# STM32.net
KiCad netlist of a schematic drawn in Altium Designer
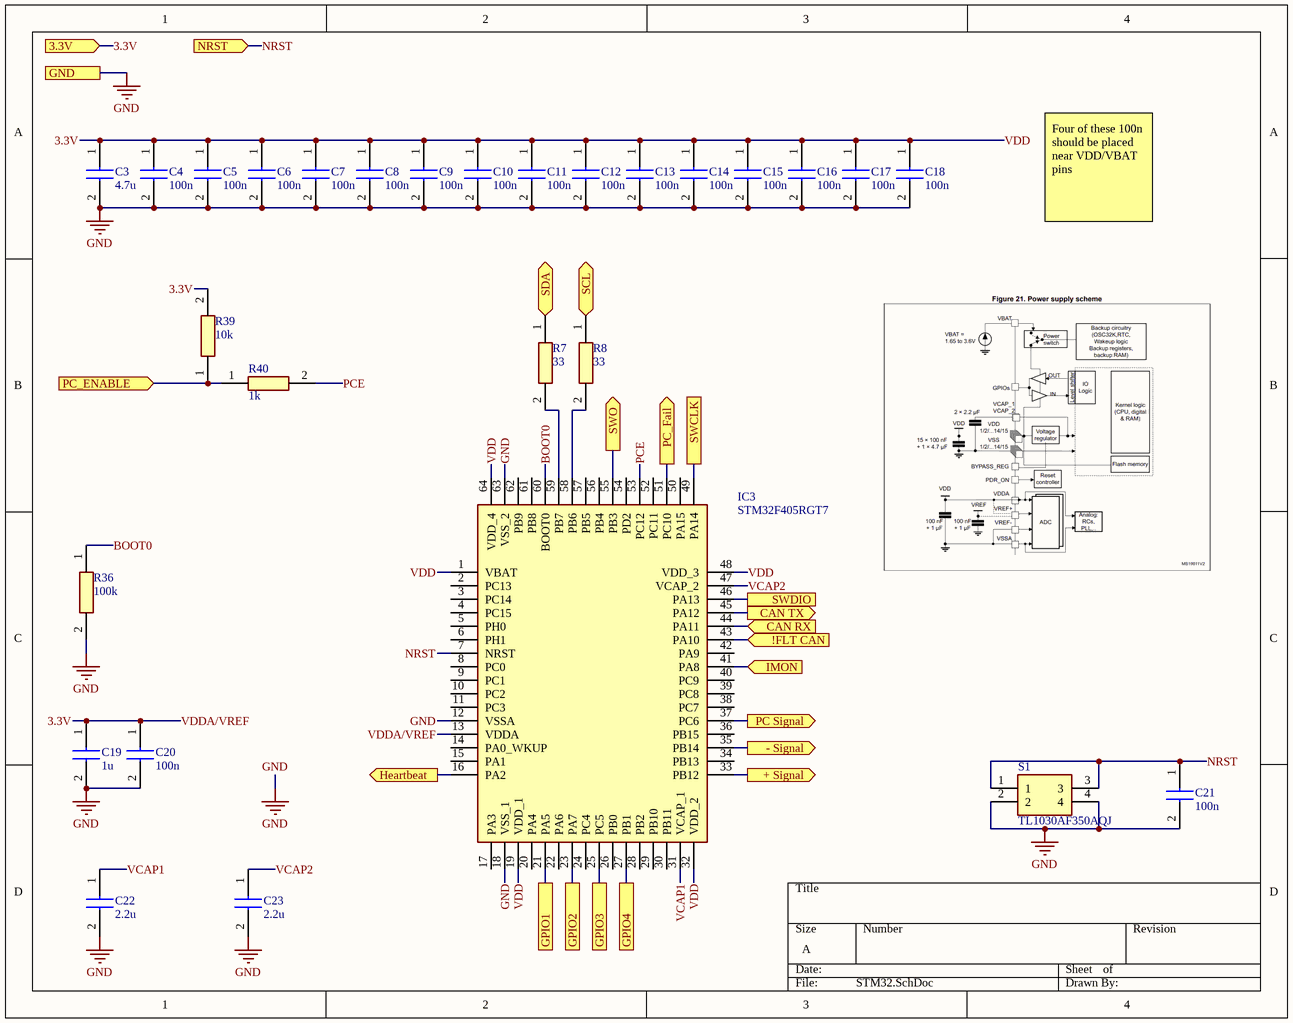
[diagram p0: STM32.SchDoc]

(export (version "E")
  (design (tool "Eeschema 10.0.6"))
  (components
    (comp (ref "C3")
      (value "4.7u")
      (footprint "SamacSys:CAPC3216X180N")
      (description "Capacitor")
      (fields
        (field (name "MANUFACTURER_PART_NUMBER") "GMK316AB7475KLHT")
        (field (name "MOUSER PART NUMBER") "963-GMK316AB7475KLHT")
      )
      (libsource (lib "SamacSys") (part "GMK316AB7475KLHT"))
    )
    (comp (ref "C4")
      (value "100n")
      (footprint "SamacSys:CAPC3216X94N")
      (description "Capacitor")
      (fields
        (field (name "MANUFACTURER_PART_NUMBER") "12065C104J4Z2A")
        (field (name "MOUSER PART NUMBER") "581-12065C104J4Z2A")
      )
      (libsource (lib "SamacSys") (part "12065C104J4Z2A"))
    )
    (comp (ref "C5")
      (value "100n")
      (footprint "SamacSys:CAPC3216X94N")
      (description "Capacitor")
      (fields
        (field (name "MANUFACTURER_PART_NUMBER") "12065C104J4Z2A")
        (field (name "MOUSER PART NUMBER") "581-12065C104J4Z2A")
      )
      (libsource (lib "SamacSys") (part "12065C104J4Z2A"))
    )
    (comp (ref "C6")
      (value "100n")
      (footprint "SamacSys:CAPC3216X94N")
      (description "Capacitor")
      (fields
        (field (name "MANUFACTURER_PART_NUMBER") "12065C104J4Z2A")
        (field (name "MOUSER PART NUMBER") "581-12065C104J4Z2A")
      )
      (libsource (lib "SamacSys") (part "12065C104J4Z2A"))
    )
    (comp (ref "C7")
      (value "100n")
      (footprint "SamacSys:CAPC3216X94N")
      (description "Capacitor")
      (fields
        (field (name "MANUFACTURER_PART_NUMBER") "12065C104J4Z2A")
        (field (name "MOUSER PART NUMBER") "581-12065C104J4Z2A")
      )
      (libsource (lib "SamacSys") (part "12065C104J4Z2A"))
    )
    (comp (ref "C8")
      (value "100n")
      (footprint "SamacSys:CAPC3216X94N")
      (description "Capacitor")
      (fields
        (field (name "MANUFACTURER_PART_NUMBER") "12065C104J4Z2A")
        (field (name "MOUSER PART NUMBER") "581-12065C104J4Z2A")
      )
      (libsource (lib "SamacSys") (part "12065C104J4Z2A"))
    )
    (comp (ref "C9")
      (value "100n")
      (footprint "SamacSys:CAPC3216X94N")
      (description "Capacitor")
      (fields
        (field (name "MANUFACTURER_PART_NUMBER") "12065C104J4Z2A")
        (field (name "MOUSER PART NUMBER") "581-12065C104J4Z2A")
      )
      (libsource (lib "SamacSys") (part "12065C104J4Z2A"))
    )
    (comp (ref "C10")
      (value "100n")
      (footprint "SamacSys:CAPC3216X94N")
      (description "Capacitor")
      (fields
        (field (name "MANUFACTURER_PART_NUMBER") "12065C104J4Z2A")
        (field (name "MOUSER PART NUMBER") "581-12065C104J4Z2A")
      )
      (libsource (lib "SamacSys") (part "12065C104J4Z2A"))
    )
    (comp (ref "C11")
      (value "100n")
      (footprint "SamacSys:CAPC3216X94N")
      (description "Capacitor")
      (fields
        (field (name "MANUFACTURER_PART_NUMBER") "12065C104J4Z2A")
        (field (name "MOUSER PART NUMBER") "581-12065C104J4Z2A")
      )
      (libsource (lib "SamacSys") (part "12065C104J4Z2A"))
    )
    (comp (ref "C12")
      (value "100n")
      (footprint "SamacSys:CAPC3216X94N")
      (description "Capacitor")
      (fields
        (field (name "MANUFACTURER_PART_NUMBER") "12065C104J4Z2A")
        (field (name "MOUSER PART NUMBER") "581-12065C104J4Z2A")
      )
      (libsource (lib "SamacSys") (part "12065C104J4Z2A"))
    )
    (comp (ref "C13")
      (value "100n")
      (footprint "SamacSys:CAPC3216X94N")
      (description "Capacitor")
      (fields
        (field (name "MANUFACTURER_PART_NUMBER") "12065C104J4Z2A")
        (field (name "MOUSER PART NUMBER") "581-12065C104J4Z2A")
      )
      (libsource (lib "SamacSys") (part "12065C104J4Z2A"))
    )
    (comp (ref "C14")
      (value "100n")
      (footprint "SamacSys:CAPC3216X94N")
      (description "Capacitor")
      (fields
        (field (name "MANUFACTURER_PART_NUMBER") "12065C104J4Z2A")
        (field (name "MOUSER PART NUMBER") "581-12065C104J4Z2A")
      )
      (libsource (lib "SamacSys") (part "12065C104J4Z2A"))
    )
    (comp (ref "C15")
      (value "100n")
      (footprint "SamacSys:CAPC3216X94N")
      (description "Capacitor")
      (fields
        (field (name "MANUFACTURER_PART_NUMBER") "12065C104J4Z2A")
        (field (name "MOUSER PART NUMBER") "581-12065C104J4Z2A")
      )
      (libsource (lib "SamacSys") (part "12065C104J4Z2A"))
    )
    (comp (ref "C16")
      (value "100n")
      (footprint "SamacSys:CAPC3216X94N")
      (description "Capacitor")
      (fields
        (field (name "MANUFACTURER_PART_NUMBER") "12065C104J4Z2A")
        (field (name "MOUSER PART NUMBER") "581-12065C104J4Z2A")
      )
      (libsource (lib "SamacSys") (part "12065C104J4Z2A"))
    )
    (comp (ref "C17")
      (value "100n")
      (footprint "SamacSys:CAPC3216X94N")
      (description "Capacitor")
      (fields
        (field (name "MANUFACTURER_PART_NUMBER") "12065C104J4Z2A")
        (field (name "MOUSER PART NUMBER") "581-12065C104J4Z2A")
      )
      (libsource (lib "SamacSys") (part "12065C104J4Z2A"))
    )
    (comp (ref "C18")
      (value "100n")
      (footprint "SamacSys:CAPC3216X94N")
      (description "Capacitor")
      (fields
        (field (name "MANUFACTURER_PART_NUMBER") "12065C104J4Z2A")
        (field (name "MOUSER PART NUMBER") "581-12065C104J4Z2A")
      )
      (libsource (lib "SamacSys") (part "12065C104J4Z2A"))
    )
    (comp (ref "C19")
      (value "1u")
      (footprint "SamacSys:CAPC3216X180N")
      (description "Capacitor")
      (fields
        (field (name "MANUFACTURER_PART_NUMBER") "HMK316B7105KLHT")
        (field (name "MOUSER PART NUMBER") "963-HMK316B7105KLHT")
      )
      (libsource (lib "SamacSys") (part "HMK316B7105KLHT"))
    )
    (comp (ref "C20")
      (value "100n")
      (footprint "SamacSys:CAPC3216X94N")
      (description "Capacitor")
      (fields
        (field (name "MANUFACTURER_PART_NUMBER") "12065C104J4Z2A")
        (field (name "MOUSER PART NUMBER") "581-12065C104J4Z2A")
      )
      (libsource (lib "SamacSys") (part "12065C104J4Z2A"))
    )
    (comp (ref "C21")
      (value "100n")
      (footprint "SamacSys:CAPC3216X94N")
      (description "Capacitor")
      (fields
        (field (name "MANUFACTURER_PART_NUMBER") "12065C104J4Z2A")
        (field (name "MOUSER PART NUMBER") "581-12065C104J4Z2A")
      )
      (libsource (lib "SamacSys") (part "12065C104J4Z2A"))
    )
    (comp (ref "C22")
      (value "2.2u")
      (footprint "SamacSys:CAPC3216X180N")
      (description "Capacitor")
      (fields
        (field (name "MANUFACTURER_PART_NUMBER") "CL31B225KCHSNNE")
        (field (name "MOUSER PART NUMBER") "187-CL31B225KCHSNNE")
      )
      (libsource (lib "*") (part "CL31B225KCHSNNE"))
    )
    (comp (ref "C23")
      (value "2.2u")
      (footprint "SamacSys:CAPC3216X180N")
      (description "Capacitor")
      (fields
        (field (name "MANUFACTURER_PART_NUMBER") "CL31B225KCHSNNE")
        (field (name "MOUSER PART NUMBER") "187-CL31B225KCHSNNE")
      )
      (libsource (lib "*") (part "CL31B225KCHSNNE"))
    )
    (comp (ref "IC3")
      (value "STM32F405RGT7")
      (footprint "SamacSys:QFP50P1200X1200X160-64N")
      (description "Integrated Circuit")
      (fields (field (name "MOUSER PART NUMBER") "511-STM32F405RGT7"))
      (libsource (lib "*") (part "STM32F405RGT7"))
    )
    (comp (ref "R7")
      (value "33")
      (footprint "SamacSys:ERJ8ENF1000V")
      (description "Resistor")
      (fields
        (field (name "MANUFACTURER_PART_NUMBER") "ERJ-8ENF33R0V")
        (field (name "MOUSER PART NUMBER") "667-ERJ-8ENF33R0V")
      )
      (libsource (lib "SamacSys") (part "ERJ-8ENF33R0V"))
    )
    (comp (ref "R8")
      (value "33")
      (footprint "SamacSys:ERJ8ENF1000V")
      (description "Resistor")
      (fields
        (field (name "MANUFACTURER_PART_NUMBER") "ERJ-8ENF33R0V")
        (field (name "MOUSER PART NUMBER") "667-ERJ-8ENF33R0V")
      )
      (libsource (lib "SamacSys") (part "ERJ-8ENF33R0V"))
    )
    (comp (ref "R36")
      (value "100k")
      (footprint "SamacSys:RESC3216X65N")
      (description "Resistor")
      (fields (field (name "MANUFACTURER_PART_NUMBER") "MCA1206ME1003BP500"))
      (libsource (lib "*") (part "MCA1206ME1003BP500"))
    )
    (comp (ref "R39")
      (value "10k")
      (footprint "SamacSys:RESC3216X65N")
      (description "Resistor")
      (fields (field (name "MANUFACTURER_PART_NUMBER") "SFR18EZPJ103"))
      (libsource (lib "*") (part "SFR18EZPJ103"))
    )
    (comp (ref "R40")
      (value "1k")
      (footprint "SamacSys:RESC3116X65N")
      (description "Resistor")
      (fields
        (field (name "MANUFACTURER_PART_NUMBER") "CRGS1206J1K0")
        (field (name "MOUSER PART NUMBER") "279-CRGS1206J1K0")
      )
      (libsource (lib "*") (part "CRGS1206J1K0"))
    )
    (comp (ref "S1")
      (value "TL1030AF350AQJ")
      (footprint "SamacSys:TL1030AF350AQJ")
      (description "Switch")
      (fields (field (name "MOUSER PART NUMBER") "612-TL1030AF350AQJ"))
      (libsource (lib "SamacSys") (part "TL1030AF350AQJ"))
    )
  )
  (nets
    (net (code "1") (name "/!FLT CAN") (class "Default")
      (node (ref "IC3") (pin "43") (pinfunction "PA10_43") (pintype "passive"))
    )
    (net (code "2") (name "/+ Signal") (class "Default")
      (node (ref "IC3") (pin "33") (pinfunction "PB12_33") (pintype "passive"))
    )
    (net (code "3") (name "/- Signal") (class "Default")
      (node (ref "IC3") (pin "35") (pinfunction "PB14_35") (pintype "passive"))
    )
    (net (code "4") (name "/3.3V") (class "Default")
      (node (ref "C10") (pin "1") (pinfunction "1_1") (pintype "passive"))
      (node (ref "C11") (pin "1") (pinfunction "1_1") (pintype "passive"))
      (node (ref "C12") (pin "1") (pinfunction "1_1") (pintype "passive"))
      (node (ref "C13") (pin "1") (pinfunction "1_1") (pintype "passive"))
      (node (ref "C14") (pin "1") (pinfunction "1_1") (pintype "passive"))
      (node (ref "C15") (pin "1") (pinfunction "1_1") (pintype "passive"))
      (node (ref "C16") (pin "1") (pinfunction "1_1") (pintype "passive"))
      (node (ref "C17") (pin "1") (pinfunction "1_1") (pintype "passive"))
      (node (ref "C18") (pin "1") (pinfunction "1_1") (pintype "passive"))
      (node (ref "C19") (pin "1") (pinfunction "1_1") (pintype "passive"))
      (node (ref "C20") (pin "1") (pinfunction "1_1") (pintype "passive"))
      (node (ref "C3") (pin "1") (pinfunction "1_1") (pintype "passive"))
      (node (ref "C4") (pin "1") (pinfunction "1_1") (pintype "passive"))
      (node (ref "C5") (pin "1") (pinfunction "1_1") (pintype "passive"))
      (node (ref "C6") (pin "1") (pinfunction "1_1") (pintype "passive"))
      (node (ref "C7") (pin "1") (pinfunction "1_1") (pintype "passive"))
      (node (ref "C8") (pin "1") (pinfunction "1_1") (pintype "passive"))
      (node (ref "C9") (pin "1") (pinfunction "1_1") (pintype "passive"))
      (node (ref "IC3") (pin "1") (pinfunction "VBAT_1") (pintype "passive"))
      (node (ref "IC3") (pin "13") (pinfunction "VDDA_13") (pintype "passive"))
      (node (ref "IC3") (pin "19") (pinfunction "VDD_1_19") (pintype "passive"))
      (node (ref "IC3") (pin "32") (pinfunction "VDD_2_32") (pintype "passive"))
      (node (ref "IC3") (pin "48") (pinfunction "VDD_3_48") (pintype "passive"))
      (node (ref "IC3") (pin "64") (pinfunction "VDD_4_64") (pintype "passive"))
      (node (ref "R39") (pin "2") (pinfunction "2_2") (pintype "passive"))
    )
    (net (code "5") (name "/BOOT0") (class "Default")
      (node (ref "IC3") (pin "60") (pinfunction "BOOT0_60") (pintype "passive"))
      (node (ref "R36") (pin "1") (pinfunction "1_1") (pintype "passive"))
    )
    (net (code "6") (name "/CAN RX") (class "Default")
      (node (ref "IC3") (pin "44") (pinfunction "PA11_44") (pintype "passive"))
    )
    (net (code "7") (name "/CAN TX") (class "Default")
      (node (ref "IC3") (pin "45") (pinfunction "PA12_45") (pintype "passive"))
    )
    (net (code "8") (name "/GPIO1") (class "Default")
      (node (ref "IC3") (pin "21") (pinfunction "PA5_21") (pintype "passive"))
    )
    (net (code "9") (name "/GPIO2") (class "Default")
      (node (ref "IC3") (pin "23") (pinfunction "PA7_23") (pintype "passive"))
    )
    (net (code "10") (name "/GPIO3") (class "Default")
      (node (ref "IC3") (pin "25") (pinfunction "PC5_25") (pintype "passive"))
    )
    (net (code "11") (name "/GPIO4") (class "Default")
      (node (ref "IC3") (pin "27") (pinfunction "PB1_27") (pintype "passive"))
    )
    (net (code "12") (name "/Heartbeat") (class "Default")
      (node (ref "IC3") (pin "16") (pinfunction "PA2_16") (pintype "passive"))
    )
    (net (code "13") (name "/IMON") (class "Default")
      (node (ref "IC3") (pin "41") (pinfunction "PA8_41") (pintype "passive"))
    )
    (net (code "14") (name "/NRST") (class "Default")
      (node (ref "C21") (pin "1") (pinfunction "1_1") (pintype "passive"))
      (node (ref "IC3") (pin "7") (pinfunction "NRST_7") (pintype "passive"))
      (node (ref "S1") (pin "1") (pinfunction "1_1") (pintype "passive"))
      (node (ref "S1") (pin "3") (pinfunction "3_3") (pintype "passive"))
    )
    (net (code "15") (name "/PC Signal") (class "Default")
      (node (ref "IC3") (pin "37") (pinfunction "PC6_37") (pintype "passive"))
    )
    (net (code "16") (name "/PCE") (class "Default")
      (node (ref "IC3") (pin "53") (pinfunction "PC12_53") (pintype "passive"))
      (node (ref "R40") (pin "2") (pinfunction "2_2") (pintype "passive"))
    )
    (net (code "17") (name "/PC_ENABLE") (class "Default")
      (node (ref "R39") (pin "1") (pinfunction "1_1") (pintype "passive"))
      (node (ref "R40") (pin "1") (pinfunction "1_1") (pintype "passive"))
    )
    (net (code "18") (name "/PC_Fail") (class "Default")
      (node (ref "IC3") (pin "51") (pinfunction "PC10_51") (pintype "passive"))
    )
    (net (code "19") (name "/SCL") (class "Default")
      (node (ref "R8") (pin "1") (pinfunction "1_1") (pintype "passive"))
    )
    (net (code "20") (name "/SDA") (class "Default")
      (node (ref "R7") (pin "1") (pinfunction "1_1") (pintype "passive"))
    )
    (net (code "21") (name "/SWCLK") (class "Default")
      (node (ref "IC3") (pin "49") (pinfunction "PA14_49") (pintype "passive"))
    )
    (net (code "22") (name "/SWDIO") (class "Default")
      (node (ref "IC3") (pin "46") (pinfunction "PA13_46") (pintype "passive"))
    )
    (net (code "23") (name "/SWO") (class "Default")
      (node (ref "IC3") (pin "55") (pinfunction "PB3_55") (pintype "passive"))
    )
    (net (code "24") (name "/VCAP1") (class "Default")
      (node (ref "C22") (pin "1") (pinfunction "1_1") (pintype "passive"))
      (node (ref "IC3") (pin "31") (pinfunction "VCAP_1_31") (pintype "passive"))
    )
    (net (code "25") (name "/VCAP2") (class "Default")
      (node (ref "C23") (pin "1") (pinfunction "1_1") (pintype "passive"))
      (node (ref "IC3") (pin "47") (pinfunction "VCAP_2_47") (pintype "passive"))
    )
    (net (code "26") (name "GND") (class "Default")
      (node (ref "C10") (pin "2") (pinfunction "2_2") (pintype "passive"))
      (node (ref "C11") (pin "2") (pinfunction "2_2") (pintype "passive"))
      (node (ref "C12") (pin "2") (pinfunction "2_2") (pintype "passive"))
      (node (ref "C13") (pin "2") (pinfunction "2_2") (pintype "passive"))
      (node (ref "C14") (pin "2") (pinfunction "2_2") (pintype "passive"))
      (node (ref "C15") (pin "2") (pinfunction "2_2") (pintype "passive"))
      (node (ref "C16") (pin "2") (pinfunction "2_2") (pintype "passive"))
      (node (ref "C17") (pin "2") (pinfunction "2_2") (pintype "passive"))
      (node (ref "C18") (pin "2") (pinfunction "2_2") (pintype "passive"))
      (node (ref "C19") (pin "2") (pinfunction "2_2") (pintype "passive"))
      (node (ref "C20") (pin "2") (pinfunction "2_2") (pintype "passive"))
      (node (ref "C21") (pin "2") (pinfunction "2_2") (pintype "passive"))
      (node (ref "C22") (pin "2") (pinfunction "2_2") (pintype "passive"))
      (node (ref "C23") (pin "2") (pinfunction "2_2") (pintype "passive"))
      (node (ref "C3") (pin "2") (pinfunction "2_2") (pintype "passive"))
      (node (ref "C4") (pin "2") (pinfunction "2_2") (pintype "passive"))
      (node (ref "C5") (pin "2") (pinfunction "2_2") (pintype "passive"))
      (node (ref "C6") (pin "2") (pinfunction "2_2") (pintype "passive"))
      (node (ref "C7") (pin "2") (pinfunction "2_2") (pintype "passive"))
      (node (ref "C8") (pin "2") (pinfunction "2_2") (pintype "passive"))
      (node (ref "C9") (pin "2") (pinfunction "2_2") (pintype "passive"))
      (node (ref "IC3") (pin "12") (pinfunction "VSSA_12") (pintype "passive"))
      (node (ref "IC3") (pin "18") (pinfunction "VSS_1_18") (pintype "passive"))
      (node (ref "IC3") (pin "63") (pinfunction "VSS_2_63") (pintype "passive"))
      (node (ref "R36") (pin "2") (pinfunction "2_2") (pintype "passive"))
      (node (ref "S1") (pin "2") (pinfunction "2_2") (pintype "passive"))
      (node (ref "S1") (pin "4") (pinfunction "4_4") (pintype "passive"))
    )
    (net (code "27") (name "Net-(IC3-PB6)") (class "Default")
      (node (ref "IC3") (pin "58") (pinfunction "PB6_58") (pintype "passive"))
      (node (ref "R8") (pin "2") (pinfunction "2_2") (pintype "passive"))
    )
    (net (code "28") (name "Net-(IC3-PB7)") (class "Default")
      (node (ref "IC3") (pin "59") (pinfunction "PB7_59") (pintype "passive"))
      (node (ref "R7") (pin "2") (pinfunction "2_2") (pintype "passive"))
    )
    (net (code "29") (name "unconnected-(IC3-PA0_WKUP-Pad14)") (class "Default")
      (node (ref "IC3") (pin "14") (pinfunction "PA0_WKUP_14") (pintype "passive"))
    )
    (net (code "30") (name "unconnected-(IC3-PA1-Pad15)") (class "Default")
      (node (ref "IC3") (pin "15") (pinfunction "PA1_15") (pintype "passive"))
    )
    (net (code "31") (name "unconnected-(IC3-PA3-Pad17)") (class "Default")
      (node (ref "IC3") (pin "17") (pinfunction "PA3_17") (pintype "passive"))
    )
    (net (code "32") (name "unconnected-(IC3-PA4-Pad20)") (class "Default")
      (node (ref "IC3") (pin "20") (pinfunction "PA4_20") (pintype "passive"))
    )
    (net (code "33") (name "unconnected-(IC3-PA6-Pad22)") (class "Default")
      (node (ref "IC3") (pin "22") (pinfunction "PA6_22") (pintype "passive"))
    )
    (net (code "34") (name "unconnected-(IC3-PA9-Pad42)") (class "Default")
      (node (ref "IC3") (pin "42") (pinfunction "PA9_42") (pintype "passive"))
    )
    (net (code "35") (name "unconnected-(IC3-PA15-Pad50)") (class "Default")
      (node (ref "IC3") (pin "50") (pinfunction "PA15_50") (pintype "passive"))
    )
    (net (code "36") (name "unconnected-(IC3-PB0-Pad26)") (class "Default")
      (node (ref "IC3") (pin "26") (pinfunction "PB0_26") (pintype "passive"))
    )
    (net (code "37") (name "unconnected-(IC3-PB2-Pad28)") (class "Default")
      (node (ref "IC3") (pin "28") (pinfunction "PB2_28") (pintype "passive"))
    )
    (net (code "38") (name "unconnected-(IC3-PB4-Pad56)") (class "Default")
      (node (ref "IC3") (pin "56") (pinfunction "PB4_56") (pintype "passive"))
    )
    (net (code "39") (name "unconnected-(IC3-PB5-Pad57)") (class "Default")
      (node (ref "IC3") (pin "57") (pinfunction "PB5_57") (pintype "passive"))
    )
    (net (code "40") (name "unconnected-(IC3-PB8-Pad61)") (class "Default")
      (node (ref "IC3") (pin "61") (pinfunction "PB8_61") (pintype "passive"))
    )
    (net (code "41") (name "unconnected-(IC3-PB9-Pad62)") (class "Default")
      (node (ref "IC3") (pin "62") (pinfunction "PB9_62") (pintype "passive"))
    )
    (net (code "42") (name "unconnected-(IC3-PB10-Pad29)") (class "Default")
      (node (ref "IC3") (pin "29") (pinfunction "PB10_29") (pintype "passive"))
    )
    (net (code "43") (name "unconnected-(IC3-PB11-Pad30)") (class "Default")
      (node (ref "IC3") (pin "30") (pinfunction "PB11_30") (pintype "passive"))
    )
    (net (code "44") (name "unconnected-(IC3-PB13-Pad34)") (class "Default")
      (node (ref "IC3") (pin "34") (pinfunction "PB13_34") (pintype "passive"))
    )
    (net (code "45") (name "unconnected-(IC3-PB15-Pad36)") (class "Default")
      (node (ref "IC3") (pin "36") (pinfunction "PB15_36") (pintype "passive"))
    )
    (net (code "46") (name "unconnected-(IC3-PC0-Pad8)") (class "Default")
      (node (ref "IC3") (pin "8") (pinfunction "PC0_8") (pintype "passive"))
    )
    (net (code "47") (name "unconnected-(IC3-PC1-Pad9)") (class "Default")
      (node (ref "IC3") (pin "9") (pinfunction "PC1_9") (pintype "passive"))
    )
    (net (code "48") (name "unconnected-(IC3-PC2-Pad10)") (class "Default")
      (node (ref "IC3") (pin "10") (pinfunction "PC2_10") (pintype "passive"))
    )
    (net (code "49") (name "unconnected-(IC3-PC3-Pad11)") (class "Default")
      (node (ref "IC3") (pin "11") (pinfunction "PC3_11") (pintype "passive"))
    )
    (net (code "50") (name "unconnected-(IC3-PC4-Pad24)") (class "Default")
      (node (ref "IC3") (pin "24") (pinfunction "PC4_24") (pintype "passive"))
    )
    (net (code "51") (name "unconnected-(IC3-PC7-Pad38)") (class "Default")
      (node (ref "IC3") (pin "38") (pinfunction "PC7_38") (pintype "passive"))
    )
    (net (code "52") (name "unconnected-(IC3-PC8-Pad39)") (class "Default")
      (node (ref "IC3") (pin "39") (pinfunction "PC8_39") (pintype "passive"))
    )
    (net (code "53") (name "unconnected-(IC3-PC9-Pad40)") (class "Default")
      (node (ref "IC3") (pin "40") (pinfunction "PC9_40") (pintype "passive"))
    )
    (net (code "54") (name "unconnected-(IC3-PC11-Pad52)") (class "Default")
      (node (ref "IC3") (pin "52") (pinfunction "PC11_52") (pintype "passive"))
    )
    (net (code "55") (name "unconnected-(IC3-PC13-Pad2)") (class "Default")
      (node (ref "IC3") (pin "2") (pinfunction "PC13_2") (pintype "passive"))
    )
    (net (code "56") (name "unconnected-(IC3-PC14-Pad3)") (class "Default")
      (node (ref "IC3") (pin "3") (pinfunction "PC14_3") (pintype "passive"))
    )
    (net (code "57") (name "unconnected-(IC3-PC15-Pad4)") (class "Default")
      (node (ref "IC3") (pin "4") (pinfunction "PC15_4") (pintype "passive"))
    )
    (net (code "58") (name "unconnected-(IC3-PD2-Pad54)") (class "Default")
      (node (ref "IC3") (pin "54") (pinfunction "PD2_54") (pintype "passive"))
    )
    (net (code "59") (name "unconnected-(IC3-PH0-Pad5)") (class "Default")
      (node (ref "IC3") (pin "5") (pinfunction "PH0_5") (pintype "passive"))
    )
    (net (code "60") (name "unconnected-(IC3-PH1-Pad6)") (class "Default")
      (node (ref "IC3") (pin "6") (pinfunction "PH1_6") (pintype "passive"))
    )
  )
)
